# REV001.net
KiCad netlist of a schematic drawn in EAGLE
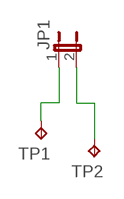
[diagram p0: schematic, sheet 1]

(export (version "E")
  (design (tool "Eeschema 10.0.6"))
  (components
    (comp (ref "JP1")
      (value "JP1E")
      (footprint "eagle-import:JP1")
      (libsource (lib "eagle-import") (part "JP1E"))
    )
    (comp (ref "TP1")
      (value "TPTP06SQ")
      (footprint "eagle-import:TP06SQ")
      (libsource (lib "eagle-import") (part "TPTP06SQ"))
    )
    (comp (ref "TP2")
      (value "TPTP06SQ")
      (footprint "eagle-import:TP06SQ")
      (libsource (lib "eagle-import") (part "TPTP06SQ"))
    )
  )
  (nets
    (net (code "1") (name "Net-(JP1-Pad1)") (class "Default")
      (node (ref "JP1") (pin "1") (pinfunction "1_1") (pintype "passive"))
      (node (ref "TP1") (pin "TP") (pinfunction "TP_TP") (pintype "input"))
    )
    (net (code "2") (name "Net-(JP1-Pad2)") (class "Default")
      (node (ref "JP1") (pin "2") (pinfunction "2_2") (pintype "passive"))
      (node (ref "TP2") (pin "TP") (pinfunction "TP_TP") (pintype "input"))
    )
  )
)
